# pixel.net
KiCad netlist of a schematic drawn in EAGLE
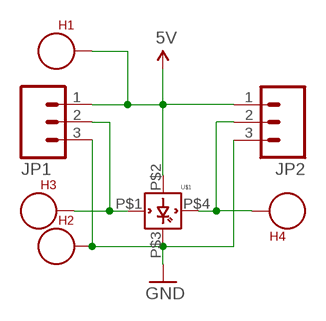
[diagram p0: schematic, sheet 1]

(export (version "E")
  (design (tool "Eeschema 10.0.6"))
  (components
    (comp (ref "H1")
      (value "SEW_HOLE")
      (footprint "eagle-import:SIMPLE_HOLE")
      (libsource (lib "eagle-import") (part "SEW_HOLE"))
    )
    (comp (ref "H2")
      (value "SEW_HOLE")
      (footprint "eagle-import:SIMPLE_HOLE")
      (libsource (lib "eagle-import") (part "SEW_HOLE"))
    )
    (comp (ref "H3")
      (value "SEW_HOLE")
      (footprint "eagle-import:SIMPLE_HOLE")
      (libsource (lib "eagle-import") (part "SEW_HOLE"))
    )
    (comp (ref "H4")
      (value "SEW_HOLE")
      (footprint "eagle-import:SIMPLE_HOLE")
      (libsource (lib "eagle-import") (part "SEW_HOLE"))
    )
    (comp (ref "JP1")
      (value "M03JST-PTH")
      (footprint "eagle-import:JST-3-PTH")
      (libsource (lib "eagle-import") (part "M03JST-PTH"))
    )
    (comp (ref "JP2")
      (value "M03JST-PTH")
      (footprint "eagle-import:JST-3-PTH")
      (libsource (lib "eagle-import") (part "M03JST-PTH"))
    )
    (comp (ref "U$1")
      (value "NEOPIXEL-PTH-5MM-CLEAR")
      (footprint "eagle-import:LED-5MM-PTH-FUCK-RA")
      (libsource (lib "eagle-import") (part "NEOPIXEL-PTH-5MM-CLEAR"))
    )
  )
  (nets
    (net (code "1") (name "5V") (class "Default")
      (node (ref "H1") (pin "P$1") (pinfunction "P$1_P$1") (pintype "bidirectional"))
      (node (ref "JP1") (pin "1") (pinfunction "1_1") (pintype "passive"))
      (node (ref "JP2") (pin "1") (pinfunction "1_1") (pintype "passive"))
      (node (ref "U$1") (pin "P$2") (pinfunction "VDD_P$2") (pintype "bidirectional"))
    )
    (net (code "2") (name "GND") (class "Default")
      (node (ref "H2") (pin "P$1") (pinfunction "P$1_P$1") (pintype "bidirectional"))
      (node (ref "JP1") (pin "3") (pinfunction "3_3") (pintype "passive"))
      (node (ref "JP2") (pin "3") (pinfunction "3_3") (pintype "passive"))
      (node (ref "U$1") (pin "P$3") (pinfunction "GND_P$3") (pintype "bidirectional"))
    )
    (net (code "3") (name "Net-(U$1-DIN)") (class "Default")
      (node (ref "H3") (pin "P$1") (pinfunction "P$1_P$1") (pintype "bidirectional"))
      (node (ref "JP1") (pin "2") (pinfunction "2_2") (pintype "passive"))
      (node (ref "U$1") (pin "P$1") (pinfunction "DIN_P$1") (pintype "input"))
    )
    (net (code "4") (name "Net-(U$1-DOUT)") (class "Default")
      (node (ref "H4") (pin "P$1") (pinfunction "P$1_P$1") (pintype "bidirectional"))
      (node (ref "JP2") (pin "2") (pinfunction "2_2") (pintype "passive"))
      (node (ref "U$1") (pin "P$4") (pinfunction "DOUT_P$4") (pintype "output"))
    )
  )
)
